# mubi-ESP32-36.net
KiCad netlist of a schematic drawn in EAGLE
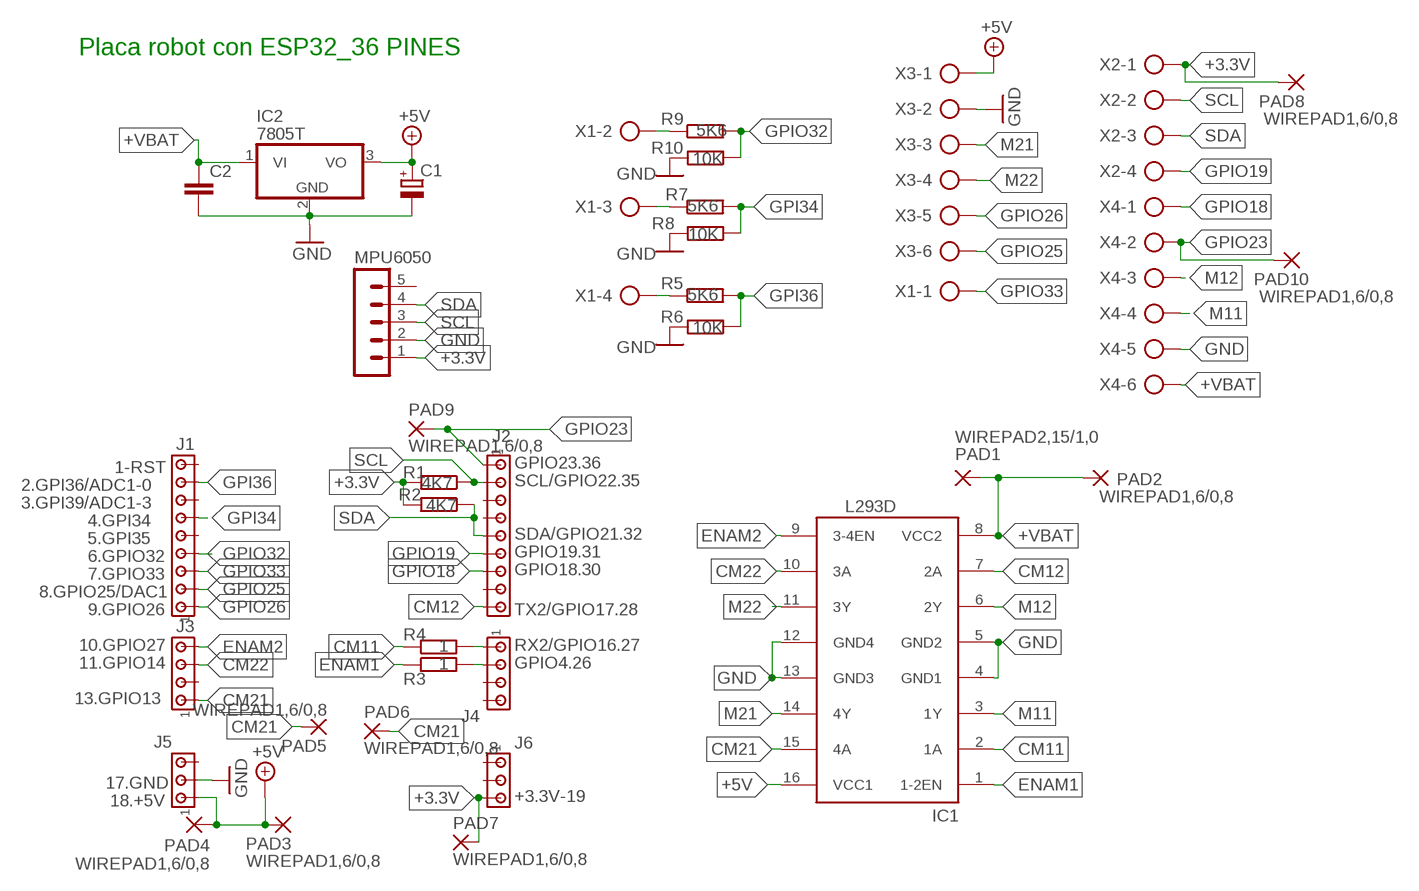
[diagram p0: schematic, sheet 1]

(export (version "E")
  (design (tool "Eeschema 10.0.6"))
  (components
    (comp (ref "C1")
      (value "CPOL-EUE2.5-6")
      (footprint "eagle-import:E2,5-6")
      (libsource (lib "eagle-import") (part "CPOL-EUE2.5-6"))
    )
    (comp (ref "C2")
      (value "C-EU025-025X050")
      (footprint "eagle-import:C025-025X050")
      (libsource (lib "eagle-import") (part "C-EU025-025X050"))
    )
    (comp (ref "IC1")
      (value "L293D")
      (footprint "eagle-import:DIL16")
      (libsource (lib "eagle-import") (part "L293D"))
    )
    (comp (ref "IC2")
      (value "7805T")
      (footprint "eagle-import:TO220H")
      (libsource (lib "eagle-import") (part "78T05"))
    )
    (comp (ref "J1")
      (value "MTA09-100")
      (footprint "eagle-import:10X09MTA")
      (libsource (lib "eagle-import") (part "MTA09-100"))
    )
    (comp (ref "J2")
      (value "MTA09-100")
      (footprint "eagle-import:10X09MTA")
      (libsource (lib "eagle-import") (part "MTA09-100"))
    )
    (comp (ref "J3")
      (value "MTA04-100")
      (footprint "eagle-import:10X04MTA")
      (libsource (lib "eagle-import") (part "MTA04-100"))
    )
    (comp (ref "J4")
      (value "MTA04-100")
      (footprint "eagle-import:10X04MTA")
      (libsource (lib "eagle-import") (part "MTA04-100"))
    )
    (comp (ref "J5")
      (value "MTA03-100")
      (footprint "eagle-import:10X03MTA")
      (libsource (lib "eagle-import") (part "MTA03-100"))
    )
    (comp (ref "J6")
      (value "MTA03-100")
      (footprint "eagle-import:10X03MTA")
      (libsource (lib "eagle-import") (part "MTA03-100"))
    )
    (comp (ref "MPU6050")
      (value "MA05-1")
      (footprint "eagle-import:MA05-1")
      (libsource (lib "eagle-import") (part "MA05-1"))
    )
    (comp (ref "PAD1")
      (value "WIREPAD2,15/1,0")
      (footprint "eagle-import:2,15_1,0")
      (libsource (lib "eagle-import") (part "WIREPAD2,15/1,0"))
    )
    (comp (ref "PAD2")
      (value "WIREPAD1,6/0,8")
      (footprint "eagle-import:1,6_0,8")
      (libsource (lib "eagle-import") (part "WIREPAD1,6/0,8"))
    )
    (comp (ref "PAD3")
      (value "WIREPAD1,6/0,8")
      (footprint "eagle-import:1,6_0,8")
      (libsource (lib "eagle-import") (part "WIREPAD1,6/0,8"))
    )
    (comp (ref "PAD4")
      (value "WIREPAD1,6/0,8")
      (footprint "eagle-import:1,6_0,8")
      (libsource (lib "eagle-import") (part "WIREPAD1,6/0,8"))
    )
    (comp (ref "PAD5")
      (value "WIREPAD1,6/0,8")
      (footprint "eagle-import:1,6_0,8")
      (libsource (lib "eagle-import") (part "WIREPAD1,6/0,8"))
    )
    (comp (ref "PAD6")
      (value "WIREPAD1,6/0,8")
      (footprint "eagle-import:1,6_0,8")
      (libsource (lib "eagle-import") (part "WIREPAD1,6/0,8"))
    )
    (comp (ref "PAD7")
      (value "WIREPAD1,6/0,8")
      (footprint "eagle-import:1,6_0,8")
      (libsource (lib "eagle-import") (part "WIREPAD1,6/0,8"))
    )
    (comp (ref "PAD8")
      (value "WIREPAD1,6/0,8")
      (footprint "eagle-import:1,6_0,8")
      (libsource (lib "eagle-import") (part "WIREPAD1,6/0,8"))
    )
    (comp (ref "PAD9")
      (value "WIREPAD1,6/0,8")
      (footprint "eagle-import:1,6_0,8")
      (libsource (lib "eagle-import") (part "WIREPAD1,6/0,8"))
    )
    (comp (ref "PAD10")
      (value "WIREPAD1,6/0,8")
      (footprint "eagle-import:1,6_0,8")
      (libsource (lib "eagle-import") (part "WIREPAD1,6/0,8"))
    )
    (comp (ref "R1")
      (value "4K7")
      (footprint "eagle-import:0207_7")
      (libsource (lib "eagle-import") (part "R-EU_0207/7"))
    )
    (comp (ref "R2")
      (value "4K7")
      (footprint "eagle-import:0207_7")
      (libsource (lib "eagle-import") (part "R-EU_0207/7"))
    )
    (comp (ref "R3")
      (value "1")
      (footprint "eagle-import:0207_10")
      (libsource (lib "eagle-import") (part "resistor_R-EU_0207/10"))
    )
    (comp (ref "R4")
      (value "1")
      (footprint "eagle-import:0207_10")
      (libsource (lib "eagle-import") (part "resistor_R-EU_0207/10"))
    )
    (comp (ref "R5")
      (value "5K6")
      (footprint "eagle-import:0204_5")
      (libsource (lib "eagle-import") (part "resistor_R-EU_0204/5"))
    )
    (comp (ref "R6")
      (value "10K")
      (footprint "eagle-import:0204_5")
      (libsource (lib "eagle-import") (part "resistor_R-EU_0204/5"))
    )
    (comp (ref "R7")
      (value "5K6")
      (footprint "eagle-import:0204_5")
      (libsource (lib "eagle-import") (part "resistor_R-EU_0204/5"))
    )
    (comp (ref "R8")
      (value "10K")
      (footprint "eagle-import:0204_5")
      (libsource (lib "eagle-import") (part "resistor_R-EU_0204/5"))
    )
    (comp (ref "R9")
      (value "5K6")
      (footprint "eagle-import:0204_5")
      (libsource (lib "eagle-import") (part "resistor_R-EU_0204/5"))
    )
    (comp (ref "R10")
      (value "10K")
      (footprint "eagle-import:0204_5")
      (libsource (lib "eagle-import") (part "resistor_R-EU_0204/5"))
    )
    (comp (ref "X1")
      (value "AK500/4-H")
      (footprint "eagle-import:AK500_4-H")
      (libsource (lib "eagle-import") (part "AK500/4-H"))
    )
    (comp (ref "X2")
      (value "AK500/4-H")
      (footprint "eagle-import:AK500_4-H")
      (libsource (lib "eagle-import") (part "AK500/4-H"))
    )
    (comp (ref "X3")
      (value "AK500/6-H")
      (footprint "eagle-import:AK500_6-H")
      (libsource (lib "eagle-import") (part "AK500/6-H"))
    )
    (comp (ref "X4")
      (value "AK500/6-H")
      (footprint "eagle-import:AK500_6-H")
      (libsource (lib "eagle-import") (part "AK500/6-H"))
    )
  )
  (nets
    (net (code "1") (name "+3.3V") (class "Default")
      (node (ref "J6") (pin "3") (pinfunction "3_3") (pintype "passive"))
      (node (ref "MPU6050") (pin "1") (pinfunction "1_1") (pintype "passive"))
      (node (ref "PAD7") (pin "1") (pinfunction "P_1") (pintype "passive"))
      (node (ref "PAD8") (pin "1") (pinfunction "P_1") (pintype "passive"))
      (node (ref "R1") (pin "2") (pinfunction "2_2") (pintype "passive"))
      (node (ref "R2") (pin "2") (pinfunction "2_2") (pintype "passive"))
      (node (ref "X2") (pin "1") (pinfunction "KL_1") (pintype "passive"))
    )
    (net (code "2") (name "+5V") (class "Default")
      (node (ref "C1") (pin "+") (pinfunction "+_+") (pintype "passive"))
      (node (ref "IC1") (pin "16") (pinfunction "VCC1_16") (pintype "power_in"))
      (node (ref "IC2") (pin "3") (pinfunction "VO_3") (pintype "passive"))
      (node (ref "J5") (pin "1") (pinfunction "1_1") (pintype "passive"))
      (node (ref "PAD3") (pin "1") (pinfunction "P_1") (pintype "passive"))
      (node (ref "PAD4") (pin "1") (pinfunction "P_1") (pintype "passive"))
      (node (ref "X3") (pin "1") (pinfunction "KL_1") (pintype "passive"))
    )
    (net (code "3") (name "+VBAT") (class "Default")
      (node (ref "C2") (pin "1") (pinfunction "1_1") (pintype "passive"))
      (node (ref "IC1") (pin "8") (pinfunction "VCC2_8") (pintype "power_in"))
      (node (ref "IC2") (pin "1") (pinfunction "VI_1") (pintype "input"))
      (node (ref "PAD1") (pin "1") (pinfunction "P_1") (pintype "passive"))
      (node (ref "PAD2") (pin "1") (pinfunction "P_1") (pintype "passive"))
      (node (ref "X4") (pin "6") (pinfunction "KL_6") (pintype "passive"))
    )
    (net (code "4") (name "CM11") (class "Default")
      (node (ref "IC1") (pin "2") (pinfunction "1A_2") (pintype "input"))
      (node (ref "R4") (pin "1") (pinfunction "1_1") (pintype "passive"))
    )
    (net (code "5") (name "CM12") (class "Default")
      (node (ref "IC1") (pin "7") (pinfunction "2A_7") (pintype "input"))
      (node (ref "J2") (pin "9") (pinfunction "9_9") (pintype "passive"))
    )
    (net (code "6") (name "CM21") (class "Default")
      (node (ref "IC1") (pin "15") (pinfunction "4A_15") (pintype "input"))
      (node (ref "J3") (pin "1") (pinfunction "1_1") (pintype "passive"))
      (node (ref "PAD5") (pin "1") (pinfunction "P_1") (pintype "passive"))
      (node (ref "PAD6") (pin "1") (pinfunction "P_1") (pintype "passive"))
    )
    (net (code "7") (name "CM22") (class "Default")
      (node (ref "IC1") (pin "10") (pinfunction "3A_10") (pintype "input"))
      (node (ref "J3") (pin "3") (pinfunction "3_3") (pintype "passive"))
    )
    (net (code "8") (name "ENAM1") (class "Default")
      (node (ref "IC1") (pin "1") (pinfunction "1-2EN_1") (pintype "input"))
      (node (ref "R3") (pin "1") (pinfunction "1_1") (pintype "passive"))
    )
    (net (code "9") (name "ENAM2") (class "Default")
      (node (ref "IC1") (pin "9") (pinfunction "3-4EN_9") (pintype "input"))
      (node (ref "J3") (pin "4") (pinfunction "4_4") (pintype "passive"))
    )
    (net (code "10") (name "GND") (class "Default")
      (node (ref "C1") (pin "-") (pinfunction "-_-") (pintype "passive"))
      (node (ref "C2") (pin "2") (pinfunction "2_2") (pintype "passive"))
      (node (ref "IC1") (pin "12") (pinfunction "GND4_12") (pintype "power_in"))
      (node (ref "IC1") (pin "13") (pinfunction "GND3_13") (pintype "power_in"))
      (node (ref "IC1") (pin "4") (pinfunction "GND1_4") (pintype "power_in"))
      (node (ref "IC1") (pin "5") (pinfunction "GND2_5") (pintype "power_in"))
      (node (ref "IC2") (pin "2") (pinfunction "GND_2") (pintype "passive"))
      (node (ref "J5") (pin "2") (pinfunction "2_2") (pintype "passive"))
      (node (ref "MPU6050") (pin "2") (pinfunction "2_2") (pintype "passive"))
      (node (ref "R10") (pin "2") (pinfunction "2_2") (pintype "passive"))
      (node (ref "R6") (pin "2") (pinfunction "2_2") (pintype "passive"))
      (node (ref "R8") (pin "2") (pinfunction "2_2") (pintype "passive"))
      (node (ref "X3") (pin "2") (pinfunction "KL_2") (pintype "passive"))
      (node (ref "X4") (pin "5") (pinfunction "KL_5") (pintype "passive"))
    )
    (net (code "11") (name "GPI34") (class "Default")
      (node (ref "J1") (pin "6") (pinfunction "6_6") (pintype "passive"))
      (node (ref "R7") (pin "2") (pinfunction "2_2") (pintype "passive"))
      (node (ref "R8") (pin "1") (pinfunction "1_1") (pintype "passive"))
    )
    (net (code "12") (name "GPI36") (class "Default")
      (node (ref "J1") (pin "8") (pinfunction "8_8") (pintype "passive"))
      (node (ref "R5") (pin "2") (pinfunction "2_2") (pintype "passive"))
      (node (ref "R6") (pin "1") (pinfunction "1_1") (pintype "passive"))
    )
    (net (code "13") (name "GPIO18") (class "Default")
      (node (ref "J2") (pin "7") (pinfunction "7_7") (pintype "passive"))
      (node (ref "X4") (pin "1") (pinfunction "KL_1") (pintype "passive"))
    )
    (net (code "14") (name "GPIO19") (class "Default")
      (node (ref "J2") (pin "6") (pinfunction "6_6") (pintype "passive"))
      (node (ref "X2") (pin "4") (pinfunction "KL_4") (pintype "passive"))
    )
    (net (code "15") (name "GPIO23") (class "Default")
      (node (ref "J2") (pin "1") (pinfunction "1_1") (pintype "passive"))
      (node (ref "PAD10") (pin "1") (pinfunction "P_1") (pintype "passive"))
      (node (ref "PAD9") (pin "1") (pinfunction "P_1") (pintype "passive"))
      (node (ref "X4") (pin "2") (pinfunction "KL_2") (pintype "passive"))
    )
    (net (code "16") (name "GPIO25") (class "Default")
      (node (ref "J1") (pin "2") (pinfunction "2_2") (pintype "passive"))
      (node (ref "X3") (pin "6") (pinfunction "KL_6") (pintype "passive"))
    )
    (net (code "17") (name "GPIO26") (class "Default")
      (node (ref "J1") (pin "1") (pinfunction "1_1") (pintype "passive"))
      (node (ref "X3") (pin "5") (pinfunction "KL_5") (pintype "passive"))
    )
    (net (code "18") (name "GPIO32") (class "Default")
      (node (ref "J1") (pin "4") (pinfunction "4_4") (pintype "passive"))
      (node (ref "R10") (pin "1") (pinfunction "1_1") (pintype "passive"))
      (node (ref "R9") (pin "2") (pinfunction "2_2") (pintype "passive"))
    )
    (net (code "19") (name "GPIO33") (class "Default")
      (node (ref "J1") (pin "3") (pinfunction "3_3") (pintype "passive"))
      (node (ref "X1") (pin "1") (pinfunction "KL_1") (pintype "passive"))
    )
    (net (code "20") (name "M11") (class "Default")
      (node (ref "IC1") (pin "3") (pinfunction "1Y_3") (pintype "output"))
      (node (ref "X4") (pin "4") (pinfunction "KL_4") (pintype "passive"))
    )
    (net (code "21") (name "M12") (class "Default")
      (node (ref "IC1") (pin "6") (pinfunction "2Y_6") (pintype "output"))
      (node (ref "X4") (pin "3") (pinfunction "KL_3") (pintype "passive"))
    )
    (net (code "22") (name "M21") (class "Default")
      (node (ref "IC1") (pin "14") (pinfunction "4Y_14") (pintype "output"))
      (node (ref "X3") (pin "3") (pinfunction "KL_3") (pintype "passive"))
    )
    (net (code "23") (name "M22") (class "Default")
      (node (ref "IC1") (pin "11") (pinfunction "3Y_11") (pintype "output"))
      (node (ref "X3") (pin "4") (pinfunction "KL_4") (pintype "passive"))
    )
    (net (code "24") (name "Net-(J4-Pad1)") (class "Default")
      (node (ref "J4") (pin "1") (pinfunction "1_1") (pintype "passive"))
      (node (ref "R4") (pin "2") (pinfunction "2_2") (pintype "passive"))
    )
    (net (code "25") (name "Net-(J4-Pad2)") (class "Default")
      (node (ref "J4") (pin "2") (pinfunction "2_2") (pintype "passive"))
      (node (ref "R3") (pin "2") (pinfunction "2_2") (pintype "passive"))
    )
    (net (code "26") (name "Net-(X1B-KL)") (class "Default")
      (node (ref "R9") (pin "1") (pinfunction "1_1") (pintype "passive"))
      (node (ref "X1") (pin "2") (pinfunction "KL_2") (pintype "passive"))
    )
    (net (code "27") (name "Net-(X1C-KL)") (class "Default")
      (node (ref "R7") (pin "1") (pinfunction "1_1") (pintype "passive"))
      (node (ref "X1") (pin "3") (pinfunction "KL_3") (pintype "passive"))
    )
    (net (code "28") (name "Net-(X1D-KL)") (class "Default")
      (node (ref "R5") (pin "1") (pinfunction "1_1") (pintype "passive"))
      (node (ref "X1") (pin "4") (pinfunction "KL_4") (pintype "passive"))
    )
    (net (code "29") (name "SCL") (class "Default")
      (node (ref "J2") (pin "2") (pinfunction "2_2") (pintype "passive"))
      (node (ref "MPU6050") (pin "3") (pinfunction "3_3") (pintype "passive"))
      (node (ref "R1") (pin "1") (pinfunction "1_1") (pintype "passive"))
      (node (ref "X2") (pin "2") (pinfunction "KL_2") (pintype "passive"))
    )
    (net (code "30") (name "SDA") (class "Default")
      (node (ref "J2") (pin "5") (pinfunction "5_5") (pintype "passive"))
      (node (ref "MPU6050") (pin "4") (pinfunction "4_4") (pintype "passive"))
      (node (ref "R2") (pin "1") (pinfunction "1_1") (pintype "passive"))
      (node (ref "X2") (pin "3") (pinfunction "KL_3") (pintype "passive"))
    )
    (net (code "31") (name "unconnected-(J1-Pad5)") (class "Default")
      (node (ref "J1") (pin "5") (pinfunction "5_5") (pintype "passive"))
    )
    (net (code "32") (name "unconnected-(J1-Pad7)") (class "Default")
      (node (ref "J1") (pin "7") (pinfunction "7_7") (pintype "passive"))
    )
    (net (code "33") (name "unconnected-(J1-Pad9)") (class "Default")
      (node (ref "J1") (pin "9") (pinfunction "9_9") (pintype "passive"))
    )
    (net (code "34") (name "unconnected-(J2-Pad3)") (class "Default")
      (node (ref "J2") (pin "3") (pinfunction "3_3") (pintype "passive"))
    )
    (net (code "35") (name "unconnected-(J2-Pad4)") (class "Default")
      (node (ref "J2") (pin "4") (pinfunction "4_4") (pintype "passive"))
    )
    (net (code "36") (name "unconnected-(J2-Pad8)") (class "Default")
      (node (ref "J2") (pin "8") (pinfunction "8_8") (pintype "passive"))
    )
    (net (code "37") (name "unconnected-(J3-Pad2)") (class "Default")
      (node (ref "J3") (pin "2") (pinfunction "2_2") (pintype "passive"))
    )
    (net (code "38") (name "unconnected-(J4-Pad3)") (class "Default")
      (node (ref "J4") (pin "3") (pinfunction "3_3") (pintype "passive"))
    )
    (net (code "39") (name "unconnected-(J4-Pad4)") (class "Default")
      (node (ref "J4") (pin "4") (pinfunction "4_4") (pintype "passive"))
    )
    (net (code "40") (name "unconnected-(J5-Pad3)") (class "Default")
      (node (ref "J5") (pin "3") (pinfunction "3_3") (pintype "passive"))
    )
    (net (code "41") (name "unconnected-(J6-Pad1)") (class "Default")
      (node (ref "J6") (pin "1") (pinfunction "1_1") (pintype "passive"))
    )
    (net (code "42") (name "unconnected-(J6-Pad2)") (class "Default")
      (node (ref "J6") (pin "2") (pinfunction "2_2") (pintype "passive"))
    )
    (net (code "43") (name "unconnected-(MPU6050-Pad5)") (class "Default")
      (node (ref "MPU6050") (pin "5") (pinfunction "5_5") (pintype "passive"))
    )
  )
)
